# flex-sensor-amplifier-hookup.net
KiCad netlist of a schematic drawn in EAGLE
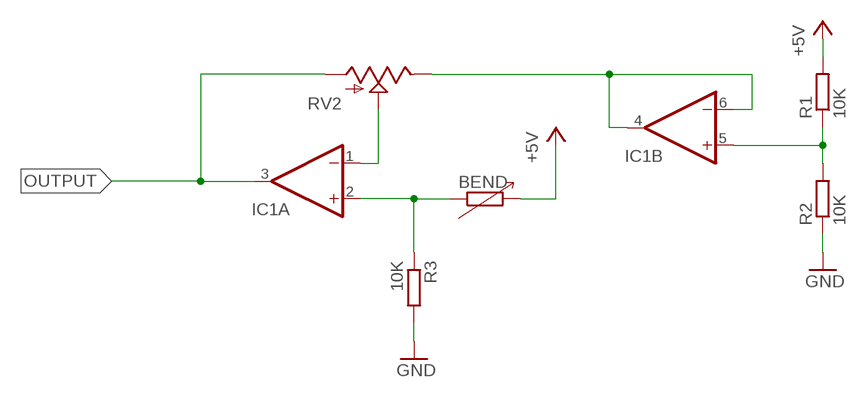
[diagram p0: schematic, sheet 1]

(export (version "E")
  (design (tool "Eeschema 10.0.6"))
  (components
    (comp (ref "BEND")
      (value "R-EU_0204/7")
      (footprint "eagle-import:0204_7")
      (libsource (lib "eagle-import") (part "R-EU_0204/7"))
    )
    (comp (ref "IC1")
      (value "4AMP_P11+7N")
      (footprint "eagle-import:DIL14")
      (libsource (lib "eagle-import") (part "4AMP_P11+7N"))
    )
    (comp (ref "R1")
      (value "10K")
      (footprint "eagle-import:0204_7")
      (libsource (lib "eagle-import") (part "R-EU_0204/7"))
    )
    (comp (ref "R2")
      (value "10K")
      (footprint "eagle-import:0204_7")
      (libsource (lib "eagle-import") (part "R-EU_0204/7"))
    )
    (comp (ref "R3")
      (value "10K")
      (footprint "eagle-import:0204_7")
      (libsource (lib "eagle-import") (part "R-EU_0204/7"))
    )
    (comp (ref "RV2")
      (value "POT")
      (footprint "eagle-import:ALPS_POT")
      (libsource (lib "eagle-import") (part "POT"))
    )
  )
  (nets
    (net (code "1") (name "+5V") (class "Default")
      (node (ref "BEND") (pin "2") (pinfunction "2_2") (pintype "passive"))
      (node (ref "R1") (pin "2") (pinfunction "2_2") (pintype "passive"))
    )
    (net (code "2") (name "GND") (class "Default")
      (node (ref "R2") (pin "1") (pinfunction "1_1") (pintype "passive"))
      (node (ref "R3") (pin "2") (pinfunction "2_2") (pintype "passive"))
    )
    (net (code "3") (name "Net-(IC1A-+IN)") (class "Default")
      (node (ref "BEND") (pin "1") (pinfunction "1_1") (pintype "passive"))
      (node (ref "IC1") (pin "2") (pinfunction "+IN_2") (pintype "input"))
      (node (ref "R3") (pin "1") (pinfunction "1_1") (pintype "passive"))
    )
    (net (code "4") (name "Net-(IC1A--IN)") (class "Default")
      (node (ref "IC1") (pin "1") (pinfunction "-IN_1") (pintype "input"))
      (node (ref "RV2") (pin "P$2") (pinfunction "S_P$2") (pintype "passive"))
    )
    (net (code "5") (name "Net-(IC1B-+IN)") (class "Default")
      (node (ref "IC1") (pin "5") (pinfunction "+IN_5") (pintype "input"))
      (node (ref "R1") (pin "1") (pinfunction "1_1") (pintype "passive"))
      (node (ref "R2") (pin "2") (pinfunction "2_2") (pintype "passive"))
    )
    (net (code "6") (name "Net-(IC1B--IN)") (class "Default")
      (node (ref "IC1") (pin "4") (pinfunction "OUT_4") (pintype "output"))
      (node (ref "IC1") (pin "6") (pinfunction "-IN_6") (pintype "input"))
      (node (ref "RV2") (pin "P$1") (pinfunction "E_P$1") (pintype "passive"))
    )
    (net (code "7") (name "OUTPUT") (class "Default")
      (node (ref "IC1") (pin "3") (pinfunction "OUT_3") (pintype "output"))
      (node (ref "RV2") (pin "P$3") (pinfunction "A_P$3") (pintype "passive"))
    )
  )
)
